# 2_P1_schdoc.net
KiCad netlist of a schematic drawn in Altium Designer
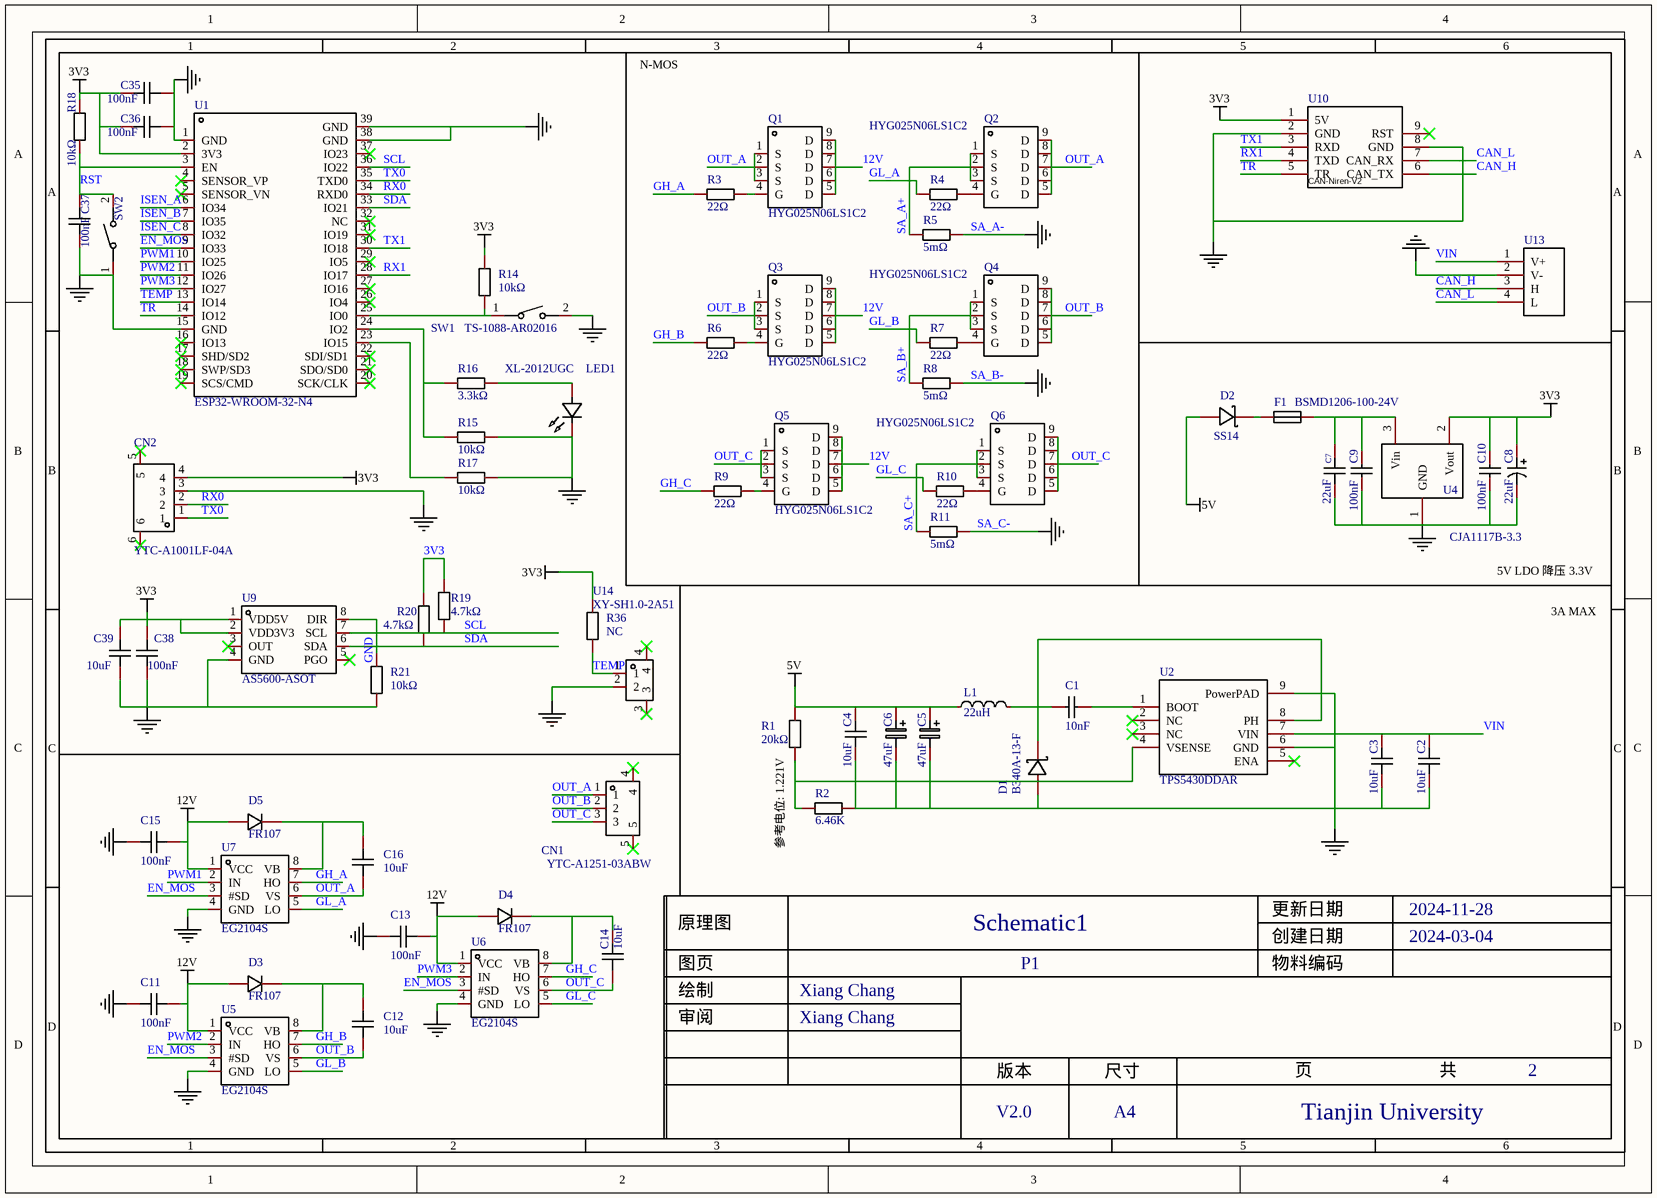
[diagram p0: 2_P1.schdoc.schdoc]

(export (version "E")
  (design (tool "Eeschema 10.0.6"))
  (components
    (comp (ref "C1")
      (value "10nF")
      (fields
        (field (name "NAME") "10nF")
        (field (name "MANUFACTURER") "YAGEO(国巨)")
        (field (name "MANUFACTURER PART") "CC0603KRX7R9BB103")
        (field (name "TOLERANCE") "±10%")
      )
      (libsource (lib "altium-import") (part "root_0_CC0603KRX7R9BB103_"))
    )
    (comp (ref "C2")
      (value "10uF")
      (fields
        (field (name "NAME") "10uF")
        (field (name "MANUFACTURER") "muRata(村田)")
        (field (name "MANUFACTURER PART") "GRM21BR61H106KE43L")
        (field (name "TOLERANCE") "±10%")
      )
      (libsource (lib "altium-import") (part "root_1_GRM21BR61H106KE43L_"))
    )
    (comp (ref "C3")
      (value "10uF")
      (fields
        (field (name "NAME") "10uF")
        (field (name "MANUFACTURER") "muRata(村田)")
        (field (name "MANUFACTURER PART") "GRM21BR61H106KE43L")
        (field (name "TOLERANCE") "±10%")
      )
      (libsource (lib "altium-import") (part "root_1_GRM21BR61H106KE43L_"))
    )
    (comp (ref "C4")
      (value "10uF")
      (fields
        (field (name "NAME") "10uF")
        (field (name "MANUFACTURER") "muRata(村田)")
        (field (name "MANUFACTURER PART") "GRM21BR61H106KE43L")
        (field (name "TOLERANCE") "±10%")
      )
      (libsource (lib "altium-import") (part "root_1_GRM21BR61H106KE43L_"))
    )
    (comp (ref "C5")
      (value "47uF")
      (fields
        (field (name "NAME") "47uF")
        (field (name "MANUFACTURER") "CEC(振华新云)")
        (field (name "MANUFACTURER PART") "CA45-B-16V-47uF-K")
        (field (name "TOLERANCE") "±10%")
      )
      (libsource (lib "altium-import") (part "root_1_CA45-B-16V-47uF-K_"))
    )
    (comp (ref "C6")
      (value "47uF")
      (fields
        (field (name "NAME") "47uF")
        (field (name "MANUFACTURER") "CEC(振华新云)")
        (field (name "MANUFACTURER PART") "CA45-B-16V-47uF-K")
        (field (name "TOLERANCE") "±10%")
      )
      (libsource (lib "altium-import") (part "root_1_CA45-B-16V-47uF-K_"))
    )
    (comp (ref "C7")
      (value "22uF")
      (fields
        (field (name "NAME") "22uF")
        (field (name "MANUFACTURER") "SAMSUNG(三星)")
        (field (name "MANUFACTURER PART") "CL10A226MO7JZNC")
        (field (name "TOLERANCE") "±20%")
      )
      (libsource (lib "altium-import") (part "root_1_CL10A226MO7JZNC_"))
    )
    (comp (ref "C8")
      (value "22uF")
      (fields
        (field (name "NAME") "22uF")
        (field (name "MANUFACTURER") "CEC(振华新云)")
        (field (name "MANUFACTURER PART") "CA45-A-16V-22uF-K")
        (field (name "TOLERANCE") "±10%")
      )
      (libsource (lib "altium-import") (part "root_3_CA45-A-16V-22uF-K_"))
    )
    (comp (ref "C9")
      (value "100nF")
      (fields
        (field (name "NAME") "100nF")
        (field (name "MANUFACTURER") "SAMSUNG(三星)")
        (field (name "MANUFACTURER PART") "CL05B104KB54PNC")
        (field (name "TOLERANCE") "±10%")
      )
      (libsource (lib "altium-import") (part "root_1_CL05B104KB54PNC_"))
    )
    (comp (ref "C10")
      (value "100nF")
      (fields
        (field (name "NAME") "100nF")
        (field (name "MANUFACTURER") "SAMSUNG(三星)")
        (field (name "MANUFACTURER PART") "CL05B104KB54PNC")
        (field (name "TOLERANCE") "±10%")
      )
      (libsource (lib "altium-import") (part "root_1_CL05B104KB54PNC_"))
    )
    (comp (ref "C11")
      (value "100nF")
      (fields
        (field (name "NAME") "100nF")
        (field (name "MANUFACTURER") "FH(风华)")
        (field (name "MANUFACTURER PART") "0603B104K500NT")
        (field (name "TOLERANCE") "±10%")
      )
      (libsource (lib "altium-import") (part "root_0_0603B104K500NT_"))
    )
    (comp (ref "C12")
      (value "10uF")
      (fields
        (field (name "NAME") "10uF")
        (field (name "MANUFACTURER") "muRata(村田)")
        (field (name "MANUFACTURER PART") "GRM21BR61H106KE43L")
        (field (name "TOLERANCE") "±10%")
      )
      (libsource (lib "altium-import") (part "root_1_GRM21BR61H106KE43L_"))
    )
    (comp (ref "C13")
      (value "100nF")
      (fields
        (field (name "NAME") "100nF")
        (field (name "MANUFACTURER") "FH(风华)")
        (field (name "MANUFACTURER PART") "0603B104K500NT")
        (field (name "TOLERANCE") "±10%")
      )
      (libsource (lib "altium-import") (part "root_0_0603B104K500NT_"))
    )
    (comp (ref "C14")
      (value "10uF")
      (fields
        (field (name "NAME") "10uF")
        (field (name "MANUFACTURER") "muRata(村田)")
        (field (name "MANUFACTURER PART") "GRM21BR61H106KE43L")
        (field (name "TOLERANCE") "±10%")
      )
      (libsource (lib "altium-import") (part "root_1_GRM21BR61H106KE43L_"))
    )
    (comp (ref "C15")
      (value "100nF")
      (fields
        (field (name "NAME") "100nF")
        (field (name "MANUFACTURER") "FH(风华)")
        (field (name "MANUFACTURER PART") "0603B104K500NT")
        (field (name "TOLERANCE") "±10%")
      )
      (libsource (lib "altium-import") (part "root_0_0603B104K500NT_"))
    )
    (comp (ref "C16")
      (value "10uF")
      (fields
        (field (name "NAME") "10uF")
        (field (name "MANUFACTURER") "muRata(村田)")
        (field (name "MANUFACTURER PART") "GRM21BR61H106KE43L")
        (field (name "TOLERANCE") "±10%")
      )
      (libsource (lib "altium-import") (part "root_1_GRM21BR61H106KE43L_"))
    )
    (comp (ref "C35")
      (value "100nF")
      (fields
        (field (name "NAME") "100nF")
        (field (name "MANUFACTURER") "FH(风华)")
        (field (name "MANUFACTURER PART") "0603B104K500NT")
        (field (name "TOLERANCE") "±10%")
      )
      (libsource (lib "altium-import") (part "root_0_0603B104K500NT_"))
    )
    (comp (ref "C36")
      (value "100nF")
      (fields
        (field (name "NAME") "100nF")
        (field (name "MANUFACTURER") "FH(风华)")
        (field (name "MANUFACTURER PART") "0603B104K500NT")
        (field (name "TOLERANCE") "±10%")
      )
      (libsource (lib "altium-import") (part "root_0_0603B104K500NT_"))
    )
    (comp (ref "C37")
      (value "100nF")
      (fields
        (field (name "NAME") "100nF")
        (field (name "MANUFACTURER") "FH(风华)")
        (field (name "MANUFACTURER PART") "0603B104K500NT")
        (field (name "TOLERANCE") "±10%")
      )
      (libsource (lib "altium-import") (part "root_1_0603B104K500NT_"))
    )
    (comp (ref "C38")
      (value "100nF")
      (fields
        (field (name "NAME") "100nF")
        (field (name "MANUFACTURER") "YAGEO(国巨)")
        (field (name "MANUFACTURER PART") "CC0603KRX7R9BB104")
        (field (name "TOLERANCE") "±10%")
      )
      (libsource (lib "altium-import") (part "root_1_CC0603KRX7R9BB104_"))
    )
    (comp (ref "C39")
      (value "10uF")
      (fields
        (field (name "NAME") "10uF")
        (field (name "MANUFACTURER") "muRata(村田)")
        (field (name "MANUFACTURER PART") "GRM21BR61H106KE43L")
        (field (name "TOLERANCE") "±10%")
      )
      (libsource (lib "altium-import") (part "root_1_GRM21BR61H106KE43L_"))
    )
    (comp (ref "CN1")
      (value "YTC-A1251-03ABW")
      (description "插针结构:1x3P;间距:1.25mm;安装方式:卧贴;总PIN数:3P;排数:1;每排PIN数:3;额定电流:1A;工作温度范围:-25℃~+85℃;")
      (fields (field (name "NAME") "YTC-A1251-03ABW") (field (name "MANUFACTURER") "YIYUAN(怡远)"))
      (libsource (lib "altium-import") (part "root_0_YTC-A1251-03ABW_"))
    )
    (comp (ref "CN2")
      (value "YTC-A1001LF-04A")
      (description "插针结构:1x4P;间距:1mm;安装方式:立贴;总PIN数:4P;排数:1;每排PIN数:4;额定电流:1A;工作温度范围:-25℃~+85℃;")
      (fields (field (name "NAME") "YTC-A1001LF-04A") (field (name "MANUFACTURER") "YIYUAN(怡远)"))
      (libsource (lib "altium-import") (part "root_2_YTC-A1001LF-04A_"))
    )
    (comp (ref "D1")
      (value "B340A-13-F")
      (description "正向压降(Vf):500mV@3A;直流反向耐压(Vr):40V;平均整流电流(Io):3A;")
      (fields (field (name "NAME") "B340A-13-F") (field (name "MANUFACTURER") "DIODES(美台)"))
      (libsource (lib "altium-import") (part "root_3_B340A-13-F_"))
    )
    (comp (ref "D2")
      (value "SS14")
      (description "二极管配置:独立式;正向压降(Vf):550mV@1A;直流反向耐压(Vr):40V;平均整流电流(Io):1A;")
      (fields (field (name "NAME") "SS14") (field (name "MANUFACTURER") "MDD"))
      (libsource (lib "altium-import") (part "root_2_SS14_C2480_"))
    )
    (comp (ref "D3")
      (value "FR107")
      (description "二极管配置:-;正向压降(Vf):1.3V@1A;直流反向耐压(Vr):1kV;平均整流电流(Io):1A;反向恢复时间(trr):500ns;")
      (fields (field (name "NAME") "FR107") (field (name "MANUFACTURER") "BORN(伯恩半导体)"))
      (libsource (lib "altium-import") (part "root_2_FR107_C511885_"))
    )
    (comp (ref "D4")
      (value "FR107")
      (description "二极管配置:-;正向压降(Vf):1.3V@1A;直流反向耐压(Vr):1kV;平均整流电流(Io):1A;反向恢复时间(trr):500ns;")
      (fields (field (name "NAME") "FR107") (field (name "MANUFACTURER") "BORN(伯恩半导体)"))
      (libsource (lib "altium-import") (part "root_2_FR107_C511885_"))
    )
    (comp (ref "D5")
      (value "FR107")
      (description "二极管配置:-;正向压降(Vf):1.3V@1A;直流反向耐压(Vr):1kV;平均整流电流(Io):1A;反向恢复时间(trr):500ns;")
      (fields (field (name "NAME") "FR107") (field (name "MANUFACTURER") "BORN(伯恩半导体)"))
      (libsource (lib "altium-import") (part "root_2_FR107_C511885_"))
    )
    (comp (ref "F1")
      (value "BSMD1206-100-24V")
      (description "最大电压:24V;最大电流:40A;保持电流:1A;跳闸电流:1.8A;")
      (fields (field (name "NAME") "BSMD1206-100-24V") (field (name "MANUFACTURER") "BHFUSE(佰宏)"))
      (libsource (lib "altium-import") (part "root_0_BSMD1206-100-24V_"))
    )
    (comp (ref "L1")
      (value "22uH")
      (fields
        (field (name "NAME") "22uH")
        (field (name "MANUFACTURER") "cjiang(长江微电)")
        (field (name "MANUFACTURER PART") "FXL0630-220-M")
        (field (name "TOLERANCE") "±20%")
      )
      (libsource (lib "altium-import") (part "root_0_FXL0630-220-M_"))
    )
    (comp (ref "LED1")
      (value "XL-2012UGC")
      (description "发光颜色:翠绿色;功率:80mW;正向电流:25mA;主波长:516nm~525nm;透镜颜色:无色透明透镜;色温:-;发光角度:120°;载带方式:正贴;工作温度:-30℃~+85℃;")
      (fields (field (name "NAME") "XL-2012UGC") (field (name "MANUFACTURER") "XINGLIGHT(成兴光)"))
      (libsource (lib "altium-import") (part "root_1_XL-2012UGC_"))
    )
    (comp (ref "Q1")
      (value "HYG025N06LS1C2")
      (fields (field (name "NAME") "HYG025N06LS1C2") (field (name "MANUFACTURER") "HUAYI(华羿微)"))
      (libsource (lib "altium-import") (part "root_0_HYG025N06LS1C2_"))
    )
    (comp (ref "Q2")
      (value "HYG025N06LS1C2")
      (fields (field (name "NAME") "HYG025N06LS1C2") (field (name "MANUFACTURER") "HUAYI(华羿微)"))
      (libsource (lib "altium-import") (part "root_0_HYG025N06LS1C2_"))
    )
    (comp (ref "Q3")
      (value "HYG025N06LS1C2")
      (fields (field (name "NAME") "HYG025N06LS1C2") (field (name "MANUFACTURER") "HUAYI(华羿微)"))
      (libsource (lib "altium-import") (part "root_0_HYG025N06LS1C2_"))
    )
    (comp (ref "Q4")
      (value "HYG025N06LS1C2")
      (fields (field (name "NAME") "HYG025N06LS1C2") (field (name "MANUFACTURER") "HUAYI(华羿微)"))
      (libsource (lib "altium-import") (part "root_0_HYG025N06LS1C2_"))
    )
    (comp (ref "Q5")
      (value "HYG025N06LS1C2")
      (fields (field (name "NAME") "HYG025N06LS1C2") (field (name "MANUFACTURER") "HUAYI(华羿微)"))
      (libsource (lib "altium-import") (part "root_0_HYG025N06LS1C2_"))
    )
    (comp (ref "Q6")
      (value "HYG025N06LS1C2")
      (fields (field (name "NAME") "HYG025N06LS1C2") (field (name "MANUFACTURER") "HUAYI(华羿微)"))
      (libsource (lib "altium-import") (part "root_0_HYG025N06LS1C2_"))
    )
    (comp (ref "R1")
      (value "20kΩ")
      (fields
        (field (name "NAME") "20kΩ")
        (field (name "MANUFACTURER") "UNI-ROYAL(厚声)")
        (field (name "MANUFACTURER PART") "0603WAF2002T5E")
        (field (name "TOLERANCE") "±1%")
      )
      (libsource (lib "altium-import") (part "root_1_0603WAF2002T5E_"))
    )
    (comp (ref "R2")
      (value "6.46K")
      (fields (field (name "NAME") "6.46K"))
      (libsource (lib "altium-import") (part "root_2_Res_0603_"))
    )
    (comp (ref "R3")
      (value "22Ω")
      (fields
        (field (name "NAME") "22Ω")
        (field (name "MANUFACTURER") "UNI-ROYAL(厚声)")
        (field (name "MANUFACTURER PART") "0603WAF220JT5E")
        (field (name "TOLERANCE") "±1%")
      )
      (libsource (lib "altium-import") (part "root_0_0603WAF220JT5E_"))
    )
    (comp (ref "R4")
      (value "22Ω")
      (fields
        (field (name "NAME") "22Ω")
        (field (name "MANUFACTURER") "UNI-ROYAL(厚声)")
        (field (name "MANUFACTURER PART") "0603WAF220JT5E")
        (field (name "TOLERANCE") "±1%")
      )
      (libsource (lib "altium-import") (part "root_0_0603WAF220JT5E_"))
    )
    (comp (ref "R5")
      (value "5mΩ")
      (fields
        (field (name "NAME") "5mΩ")
        (field (name "MANUFACTURER") "大毅科技")
        (field (name "MANUFACTURER PART") "RLP25FEGMR005")
        (field (name "TOLERANCE") "±1%")
      )
      (libsource (lib "altium-import") (part "root_2_RLP25FEGMR005_"))
    )
    (comp (ref "R6")
      (value "22Ω")
      (fields
        (field (name "NAME") "22Ω")
        (field (name "MANUFACTURER") "UNI-ROYAL(厚声)")
        (field (name "MANUFACTURER PART") "0603WAF220JT5E")
        (field (name "TOLERANCE") "±1%")
      )
      (libsource (lib "altium-import") (part "root_0_0603WAF220JT5E_"))
    )
    (comp (ref "R7")
      (value "22Ω")
      (fields
        (field (name "NAME") "22Ω")
        (field (name "MANUFACTURER") "UNI-ROYAL(厚声)")
        (field (name "MANUFACTURER PART") "0603WAF220JT5E")
        (field (name "TOLERANCE") "±1%")
      )
      (libsource (lib "altium-import") (part "root_0_0603WAF220JT5E_"))
    )
    (comp (ref "R8")
      (value "5mΩ")
      (fields
        (field (name "NAME") "5mΩ")
        (field (name "MANUFACTURER") "大毅科技")
        (field (name "MANUFACTURER PART") "RLP25FEGMR005")
        (field (name "TOLERANCE") "±1%")
      )
      (libsource (lib "altium-import") (part "root_2_RLP25FEGMR005_"))
    )
    (comp (ref "R9")
      (value "22Ω")
      (fields
        (field (name "NAME") "22Ω")
        (field (name "MANUFACTURER") "UNI-ROYAL(厚声)")
        (field (name "MANUFACTURER PART") "0603WAF220JT5E")
        (field (name "TOLERANCE") "±1%")
      )
      (libsource (lib "altium-import") (part "root_0_0603WAF220JT5E_"))
    )
    (comp (ref "R10")
      (value "22Ω")
      (fields
        (field (name "NAME") "22Ω")
        (field (name "MANUFACTURER") "UNI-ROYAL(厚声)")
        (field (name "MANUFACTURER PART") "0603WAF220JT5E")
        (field (name "TOLERANCE") "±1%")
      )
      (libsource (lib "altium-import") (part "root_0_0603WAF220JT5E_"))
    )
    (comp (ref "R11")
      (value "5mΩ")
      (fields
        (field (name "NAME") "5mΩ")
        (field (name "MANUFACTURER") "大毅科技")
        (field (name "MANUFACTURER PART") "RLP25FEGMR005")
        (field (name "TOLERANCE") "±1%")
      )
      (libsource (lib "altium-import") (part "root_2_RLP25FEGMR005_"))
    )
    (comp (ref "R14")
      (value "10kΩ")
      (fields
        (field (name "NAME") "10kΩ")
        (field (name "MANUFACTURER") "UNI-ROYAL(厚声)")
        (field (name "MANUFACTURER PART") "0603WAF1002T5E")
        (field (name "TOLERANCE") "±1%")
      )
      (libsource (lib "altium-import") (part "root_1_0603WAF1002T5E_"))
    )
    (comp (ref "R15")
      (value "10kΩ")
      (fields
        (field (name "NAME") "10kΩ")
        (field (name "MANUFACTURER") "UNI-ROYAL(厚声)")
        (field (name "MANUFACTURER PART") "0603WAF1002T5E")
        (field (name "TOLERANCE") "±1%")
      )
      (libsource (lib "altium-import") (part "root_0_0603WAF1002T5E_"))
    )
    (comp (ref "R16")
      (value "3.3kΩ")
      (fields
        (field (name "NAME") "3.3kΩ")
        (field (name "MANUFACTURER") "UNI-ROYAL(厚声)")
        (field (name "MANUFACTURER PART") "0603WAF3301T5E")
        (field (name "TOLERANCE") "±1%")
      )
      (libsource (lib "altium-import") (part "root_0_0603WAF3301T5E_"))
    )
    (comp (ref "R17")
      (value "10kΩ")
      (fields
        (field (name "NAME") "10kΩ")
        (field (name "MANUFACTURER") "UNI-ROYAL(厚声)")
        (field (name "MANUFACTURER PART") "0603WAF1002T5E")
        (field (name "TOLERANCE") "±1%")
      )
      (libsource (lib "altium-import") (part "root_0_0603WAF1002T5E_"))
    )
    (comp (ref "R18")
      (value "10kΩ")
      (fields
        (field (name "NAME") "10kΩ")
        (field (name "MANUFACTURER") "UNI-ROYAL(厚声)")
        (field (name "MANUFACTURER PART") "0603WAF1002T5E")
        (field (name "TOLERANCE") "±1%")
      )
      (libsource (lib "altium-import") (part "root_1_0603WAF1002T5E_"))
    )
    (comp (ref "R19")
      (value "4.7kΩ")
      (fields
        (field (name "NAME") "4.7kΩ")
        (field (name "MANUFACTURER") "UNI-ROYAL(厚声)")
        (field (name "MANUFACTURER PART") "0603WAF4701T5E")
        (field (name "TOLERANCE") "±1%")
      )
      (libsource (lib "altium-import") (part "root_1_0603WAF4701T5E_"))
    )
    (comp (ref "R20")
      (value "4.7kΩ")
      (fields
        (field (name "NAME") "4.7kΩ")
        (field (name "MANUFACTURER") "UNI-ROYAL(厚声)")
        (field (name "MANUFACTURER PART") "0603WAF4701T5E")
        (field (name "TOLERANCE") "±1%")
      )
      (libsource (lib "altium-import") (part "root_1_0603WAF4701T5E_"))
    )
    (comp (ref "R21")
      (value "10kΩ")
      (fields
        (field (name "NAME") "10kΩ")
        (field (name "MANUFACTURER") "UNI-ROYAL(厚声)")
        (field (name "MANUFACTURER PART") "0603WAF1002T5E")
        (field (name "TOLERANCE") "±1%")
      )
      (libsource (lib "altium-import") (part "root_1_0603WAF1002T5E_"))
    )
    (comp (ref "R36")
      (value "NC")
      (fields (field (name "NAME") "NC"))
      (libsource (lib "altium-import") (part "root_1_Res_0603_"))
    )
    (comp (ref "SW1")
      (value "TS-1088-AR02016")
      (fields (field (name "NAME") "TS-1088-AR02016") (field (name "MANUFACTURER") "XUNPU(讯普)"))
      (libsource (lib "altium-import") (part "root_0_TS-1088-AR02016_"))
    )
    (comp (ref "SW2")
      (value "TS-1088-AR02016")
      (fields (field (name "MANUFACTURER") "XUNPU(讯普)"))
      (libsource (lib "altium-import") (part "root_1_TS-1088-AR02016_"))
    )
    (comp (ref "U1")
      (value "ESP32-WROOM-32-N4")
      (description "WiFi+蓝牙4.2+双核CPU,ESP32")
      (fields (field (name "NAME") "ESP32-WROOM-32-N4") (field (name "MANUFACTURER") "ESPRESSIF(乐鑫)"))
      (libsource (lib "altium-import") (part "root_0_ESP32-WROOM-32-N4_"))
    )
    (comp (ref "U2")
      (value "TPS5430DDAR")
      (description "功能类型:降压型;输出类型:可调;输入电压:5.5V~36V;输出电压:1.221V~32.04V;输出电流(最大值):3A;")
      (fields (field (name "NAME") "TPS5430DDAR") (field (name "MANUFACTURER") "TI(德州仪器)"))
      (libsource (lib "altium-import") (part "root_0_TPS5430DDAR_"))
    )
    (comp (ref "U4")
      (value "CJA1117B-3.3")
      (description "输出类型:固定;最大输入电压:15V;输出电压:3.3V;输出电流:1A;电源纹波抑制比(PSRR):75dB@(120Hz);输出极性:正;")
      (fields (field (name "NAME") "CJA1117B-3.3") (field (name "MANUFACTURER") "CJ(江苏长电/长晶)"))
      (libsource (lib "altium-import") (part "root_1_CJA1117B-3.3_"))
    )
    (comp (ref "U5")
      (value "EG2104S")
      (fields (field (name "NAME") "EG2104S") (field (name "MANUFACTURER") "EG(屹晶微)"))
      (libsource (lib "altium-import") (part "root_0_EG2104S_"))
    )
    (comp (ref "U6")
      (value "EG2104S")
      (fields (field (name "NAME") "EG2104S") (field (name "MANUFACTURER") "EG(屹晶微)"))
      (libsource (lib "altium-import") (part "root_0_EG2104S_"))
    )
    (comp (ref "U7")
      (value "EG2104S")
      (fields (field (name "NAME") "EG2104S") (field (name "MANUFACTURER") "EG(屹晶微)"))
      (libsource (lib "altium-import") (part "root_0_EG2104S_"))
    )
    (comp (ref "U9")
      (value "AS5600-ASOT")
      (fields (field (name "NAME") "AS5600-ASOT") (field (name "MANUFACTURER") "ams(艾迈斯半导体)"))
      (libsource (lib "altium-import") (part "root_0_AS5600-ASOT_"))
    )
    (comp (ref "U10")
      (value "CAN-Niren-V2")
      (description "CAN-Niren-V2")
      (libsource (lib "altium-import") (part "root_0_CAN-Niren-V2_"))
    )
    (comp (ref "U13")
      (value "XT30PB(2+2)-M")
      (libsource (lib "altium-import") (part "root_0_XT30PB(2+2)-M_"))
    )
    (comp (ref "U14")
      (value "XY-SH1.0-2A51")
      (description "插针结构:1x2P;间距:1mm;安装方式:立贴;总PIN数:2P;排数:1;每排PIN数:2;")
      (fields (field (name "NAME") "XY-SH1.0-2A51") (field (name "MANUFACTURER") "XYECONN(辛译)"))
      (libsource (lib "altium-import") (part "root_0_XY-SH1.0-2A51_"))
    )
  )
  (nets
    (net (code "1") (name "/CAN_H") (class "Default")
      (node (ref "U10") (pin "6") (pinfunction "CAN_TX_6") (pintype "passive"))
      (node (ref "U13") (pin "3") (pinfunction "H_3") (pintype "passive"))
    )
    (net (code "2") (name "/CAN_L") (class "Default")
      (node (ref "U10") (pin "7") (pinfunction "CAN_RX_7") (pintype "passive"))
      (node (ref "U13") (pin "4") (pinfunction "L_4") (pintype "passive"))
    )
    (net (code "3") (name "/EN_MOS") (class "Default")
      (node (ref "U1") (pin "9") (pinfunction "IO33_9") (pintype "passive"))
      (node (ref "U5") (pin "3") (pinfunction "#SD_3") (pintype "passive"))
      (node (ref "U6") (pin "3") (pinfunction "#SD_3") (pintype "passive"))
      (node (ref "U7") (pin "3") (pinfunction "#SD_3") (pintype "passive"))
    )
    (net (code "4") (name "/GH_A") (class "Default")
      (node (ref "R3") (pin "1") (pinfunction "1_1") (pintype "passive"))
      (node (ref "U7") (pin "7") (pinfunction "HO_7") (pintype "passive"))
    )
    (net (code "5") (name "/GH_B") (class "Default")
      (node (ref "R6") (pin "1") (pinfunction "1_1") (pintype "passive"))
      (node (ref "U5") (pin "7") (pinfunction "HO_7") (pintype "passive"))
    )
    (net (code "6") (name "/GH_C") (class "Default")
      (node (ref "R9") (pin "1") (pinfunction "1_1") (pintype "passive"))
      (node (ref "U6") (pin "7") (pinfunction "HO_7") (pintype "passive"))
    )
    (net (code "7") (name "/GL_A") (class "Default")
      (node (ref "R4") (pin "1") (pinfunction "1_1") (pintype "passive"))
      (node (ref "U7") (pin "5") (pinfunction "LO_5") (pintype "passive"))
    )
    (net (code "8") (name "/GL_B") (class "Default")
      (node (ref "R7") (pin "1") (pinfunction "1_1") (pintype "passive"))
      (node (ref "U5") (pin "5") (pinfunction "LO_5") (pintype "passive"))
    )
    (net (code "9") (name "/GL_C") (class "Default")
      (node (ref "R10") (pin "1") (pinfunction "1_1") (pintype "passive"))
      (node (ref "U6") (pin "5") (pinfunction "LO_5") (pintype "passive"))
    )
    (net (code "10") (name "/ISEN_A") (class "Default")
      (node (ref "U1") (pin "6") (pinfunction "IO34_6") (pintype "passive"))
    )
    (net (code "11") (name "/ISEN_B") (class "Default")
      (node (ref "U1") (pin "7") (pinfunction "IO35_7") (pintype "passive"))
    )
    (net (code "12") (name "/ISEN_C") (class "Default")
      (node (ref "U1") (pin "8") (pinfunction "IO32_8") (pintype "passive"))
    )
    (net (code "13") (name "/OUT_A") (class "Default")
      (node (ref "C16") (pin "1") (pinfunction "1_1") (pintype "passive"))
      (node (ref "CN1") (pin "1") (pinfunction "1_1") (pintype "passive"))
      (node (ref "Q1") (pin "1") (pinfunction "S_1") (pintype "passive"))
      (node (ref "Q1") (pin "2") (pinfunction "S_2") (pintype "passive"))
      (node (ref "Q1") (pin "3") (pinfunction "S_3") (pintype "passive"))
      (node (ref "Q2") (pin "5") (pinfunction "D_5") (pintype "passive"))
      (node (ref "Q2") (pin "6") (pinfunction "D_6") (pintype "passive"))
      (node (ref "Q2") (pin "7") (pinfunction "D_7") (pintype "passive"))
      (node (ref "Q2") (pin "8") (pinfunction "D_8") (pintype "passive"))
      (node (ref "Q2") (pin "9") (pinfunction "D_9") (pintype "passive"))
      (node (ref "U7") (pin "6") (pinfunction "VS_6") (pintype "passive"))
    )
    (net (code "14") (name "/OUT_B") (class "Default")
      (node (ref "C12") (pin "1") (pinfunction "1_1") (pintype "passive"))
      (node (ref "CN1") (pin "2") (pinfunction "2_2") (pintype "passive"))
      (node (ref "Q3") (pin "1") (pinfunction "S_1") (pintype "passive"))
      (node (ref "Q3") (pin "2") (pinfunction "S_2") (pintype "passive"))
      (node (ref "Q3") (pin "3") (pinfunction "S_3") (pintype "passive"))
      (node (ref "Q4") (pin "5") (pinfunction "D_5") (pintype "passive"))
      (node (ref "Q4") (pin "6") (pinfunction "D_6") (pintype "passive"))
      (node (ref "Q4") (pin "7") (pinfunction "D_7") (pintype "passive"))
      (node (ref "Q4") (pin "8") (pinfunction "D_8") (pintype "passive"))
      (node (ref "Q4") (pin "9") (pinfunction "D_9") (pintype "passive"))
      (node (ref "U5") (pin "6") (pinfunction "VS_6") (pintype "passive"))
    )
    (net (code "15") (name "/OUT_C") (class "Default")
      (node (ref "C14") (pin "1") (pinfunction "1_1") (pintype "passive"))
      (node (ref "CN1") (pin "3") (pinfunction "3_3") (pintype "passive"))
      (node (ref "Q5") (pin "1") (pinfunction "S_1") (pintype "passive"))
      (node (ref "Q5") (pin "2") (pinfunction "S_2") (pintype "passive"))
      (node (ref "Q5") (pin "3") (pinfunction "S_3") (pintype "passive"))
      (node (ref "Q6") (pin "5") (pinfunction "D_5") (pintype "passive"))
      (node (ref "Q6") (pin "6") (pinfunction "D_6") (pintype "passive"))
      (node (ref "Q6") (pin "7") (pinfunction "D_7") (pintype "passive"))
      (node (ref "Q6") (pin "8") (pinfunction "D_8") (pintype "passive"))
      (node (ref "Q6") (pin "9") (pinfunction "D_9") (pintype "passive"))
      (node (ref "U6") (pin "6") (pinfunction "VS_6") (pintype "passive"))
    )
    (net (code "16") (name "/PWM1") (class "Default")
      (node (ref "U1") (pin "10") (pinfunction "IO25_10") (pintype "passive"))
      (node (ref "U7") (pin "2") (pinfunction "IN_2") (pintype "passive"))
    )
    (net (code "17") (name "/PWM2") (class "Default")
      (node (ref "U1") (pin "11") (pinfunction "IO26_11") (pintype "passive"))
      (node (ref "U5") (pin "2") (pinfunction "IN_2") (pintype "passive"))
    )
    (net (code "18") (name "/PWM3") (class "Default")
      (node (ref "U1") (pin "12") (pinfunction "IO27_12") (pintype "passive"))
      (node (ref "U6") (pin "2") (pinfunction "IN_2") (pintype "passive"))
    )
    (net (code "19") (name "/RST") (class "Default")
      (node (ref "C37") (pin "2") (pinfunction "2_2") (pintype "passive"))
      (node (ref "R18") (pin "1") (pinfunction "1_1") (pintype "passive"))
      (node (ref "SW2") (pin "2") (pinfunction "2_2") (pintype "passive"))
      (node (ref "U1") (pin "3") (pinfunction "EN_3") (pintype "passive"))
    )
    (net (code "20") (name "/RX0") (class "Default")
      (node (ref "CN2") (pin "2") (pinfunction "2_2") (pintype "passive"))
      (node (ref "U1") (pin "34") (pinfunction "RXD0_34") (pintype "passive"))
    )
    (net (code "21") (name "/RX1") (class "Default")
      (node (ref "U1") (pin "28") (pinfunction "IO17_28") (pintype "passive"))
      (node (ref "U10") (pin "4") (pinfunction "TXD_4") (pintype "passive"))
    )
    (net (code "22") (name "/SA_A+") (class "Default")
      (node (ref "Q2") (pin "1") (pinfunction "S_1") (pintype "passive"))
      (node (ref "Q2") (pin "2") (pinfunction "S_2") (pintype "passive"))
      (node (ref "Q2") (pin "3") (pinfunction "S_3") (pintype "passive"))
      (node (ref "R5") (pin "2") (pinfunction "2_2") (pintype "passive"))
    )
    (net (code "23") (name "/SA_B+") (class "Default")
      (node (ref "Q4") (pin "1") (pinfunction "S_1") (pintype "passive"))
      (node (ref "Q4") (pin "2") (pinfunction "S_2") (pintype "passive"))
      (node (ref "Q4") (pin "3") (pinfunction "S_3") (pintype "passive"))
      (node (ref "R8") (pin "2") (pinfunction "2_2") (pintype "passive"))
    )
    (net (code "24") (name "/SA_C+") (class "Default")
      (node (ref "Q6") (pin "1") (pinfunction "S_1") (pintype "passive"))
      (node (ref "Q6") (pin "2") (pinfunction "S_2") (pintype "passive"))
      (node (ref "Q6") (pin "3") (pinfunction "S_3") (pintype "passive"))
      (node (ref "R11") (pin "2") (pinfunction "2_2") (pintype "passive"))
    )
    (net (code "25") (name "/SCL") (class "Default")
      (node (ref "R19") (pin "1") (pinfunction "1_1") (pintype "passive"))
      (node (ref "U1") (pin "36") (pinfunction "IO22_36") (pintype "passive"))
      (node (ref "U9") (pin "7") (pinfunction "SCL_7") (pintype "passive"))
    )
    (net (code "26") (name "/SDA") (class "Default")
      (node (ref "R20") (pin "1") (pinfunction "1_1") (pintype "passive"))
      (node (ref "U1") (pin "33") (pinfunction "IO21_33") (pintype "passive"))
      (node (ref "U9") (pin "6") (pinfunction "SDA_6") (pintype "passive"))
    )
    (net (code "27") (name "/TEMP") (class "Default")
      (node (ref "R36") (pin "1") (pinfunction "1_1") (pintype "passive"))
      (node (ref "U1") (pin "13") (pinfunction "IO14_13") (pintype "passive"))
      (node (ref "U14") (pin "1") (pinfunction "1_1") (pintype "passive"))
    )
    (net (code "28") (name "/TR") (class "Default")
      (node (ref "U1") (pin "14") (pinfunction "IO12_14") (pintype "passive"))
      (node (ref "U10") (pin "5") (pinfunction "TR_5") (pintype "passive"))
    )
    (net (code "29") (name "/TX0") (class "Default")
      (node (ref "CN2") (pin "1") (pinfunction "1_1") (pintype "passive"))
      (node (ref "U1") (pin "35") (pinfunction "TXD0_35") (pintype "passive"))
    )
    (net (code "30") (name "/TX1") (class "Default")
      (node (ref "U1") (pin "30") (pinfunction "IO18_30") (pintype "passive"))
      (node (ref "U10") (pin "3") (pinfunction "RXD_3") (pintype "passive"))
    )
    (net (code "31") (name "/VIN") (class "Default")
      (node (ref "C2") (pin "2") (pinfunction "2_2") (pintype "passive"))
      (node (ref "C3") (pin "2") (pinfunction "2_2") (pintype "passive"))
      (node (ref "U13") (pin "1") (pinfunction "V+_1") (pintype "passive"))
      (node (ref "U2") (pin "7") (pinfunction "VIN_7") (pintype "passive"))
    )
    (net (code "32") (name "3V3") (class "Default")
      (node (ref "C10") (pin "2") (pinfunction "2_2") (pintype "passive"))
      (node (ref "C35") (pin "1") (pinfunction "1_1") (pintype "passive"))
      (node (ref "C36") (pin "1") (pinfunction "1_1") (pintype "passive"))
      (node (ref "C38") (pin "2") (pinfunction "2_2") (pintype "passive"))
      (node (ref "C39") (pin "2") (pinfunction "2_2") (pintype "passive"))
      (node (ref "C8") (pin "1") (pinfunction "1_1") (pintype "passive"))
      (node (ref "CN2") (pin "4") (pinfunction "4_4") (pintype "passive"))
      (node (ref "R14") (pin "2") (pinfunction "2_2") (pintype "passive"))
      (node (ref "R18") (pin "2") (pinfunction "2_2") (pintype "passive"))
      (node (ref "R19") (pin "2") (pinfunction "2_2") (pintype "passive"))
      (node (ref "R20") (pin "2") (pinfunction "2_2") (pintype "passive"))
      (node (ref "R36") (pin "2") (pinfunction "2_2") (pintype "passive"))
      (node (ref "U1") (pin "2") (pinfunction "3V3_2") (pintype "passive"))
      (node (ref "U10") (pin "1") (pinfunction "5V_1") (pintype "passive"))
      (node (ref "U4") (pin "2") (pinfunction "Vout_2") (pintype "passive"))
      (node (ref "U9") (pin "1") (pinfunction "VDD5V_1") (pintype "passive"))
      (node (ref "U9") (pin "2") (pinfunction "VDD3V3_2") (pintype "passive"))
    )
    (net (code "33") (name "5V") (class "Default")
      (node (ref "C4") (pin "2") (pinfunction "2_2") (pintype "passive"))
      (node (ref "C5") (pin "1") (pinfunction "1_1") (pintype "passive"))
      (node (ref "C6") (pin "1") (pinfunction "1_1") (pintype "passive"))
      (node (ref "D2") (pin "2") (pinfunction "A_2") (pintype "passive"))
      (node (ref "L1") (pin "1") (pinfunction "1_1") (pintype "passive"))
      (node (ref "R1") (pin "2") (pinfunction "2_2") (pintype "passive"))
    )
    (net (code "34") (name "12V") (class "Default")
      (node (ref "C11") (pin "2") (pinfunction "2_2") (pintype "passive"))
      (node (ref "C13") (pin "2") (pinfunction "2_2") (pintype "passive"))
      (node (ref "C15") (pin "2") (pinfunction "2_2") (pintype "passive"))
      (node (ref "D3") (pin "2") (pinfunction "A_2") (pintype "passive"))
      (node (ref "D4") (pin "2") (pinfunction "A_2") (pintype "passive"))
      (node (ref "D5") (pin "2") (pinfunction "A_2") (pintype "passive"))
      (node (ref "Q1") (pin "5") (pinfunction "D_5") (pintype "passive"))
      (node (ref "Q1") (pin "6") (pinfunction "D_6") (pintype "passive"))
      (node (ref "Q1") (pin "7") (pinfunction "D_7") (pintype "passive"))
      (node (ref "Q1") (pin "8") (pinfunction "D_8") (pintype "passive"))
      (node (ref "Q1") (pin "9") (pinfunction "D_9") (pintype "passive"))
      (node (ref "Q3") (pin "5") (pinfunction "D_5") (pintype "passive"))
      (node (ref "Q3") (pin "6") (pinfunction "D_6") (pintype "passive"))
      (node (ref "Q3") (pin "7") (pinfunction "D_7") (pintype "passive"))
      (node (ref "Q3") (pin "8") (pinfunction "D_8") (pintype "passive"))
      (node (ref "Q3") (pin "9") (pinfunction "D_9") (pintype "passive"))
      (node (ref "Q5") (pin "5") (pinfunction "D_5") (pintype "passive"))
      (node (ref "Q5") (pin "6") (pinfunction "D_6") (pintype "passive"))
      (node (ref "Q5") (pin "7") (pinfunction "D_7") (pintype "passive"))
      (node (ref "Q5") (pin "8") (pinfunction "D_8") (pintype "passive"))
      (node (ref "Q5") (pin "9") (pinfunction "D_9") (pintype "passive"))
      (node (ref "U5") (pin "1") (pinfunction "VCC_1") (pintype "passive"))
      (node (ref "U6") (pin "1") (pinfunction "VCC_1") (pintype "passive"))
      (node (ref "U7") (pin "1") (pinfunction "VCC_1") (pintype "passive"))
    )
    (net (code "35") (name "GND") (class "Default")
      (node (ref "C10") (pin "1") (pinfunction "1_1") (pintype "passive"))
      (node (ref "C11") (pin "1") (pinfunction "1_1") (pintype "passive"))
      (node (ref "C13") (pin "1") (pinfunction "1_1") (pintype "passive"))
      (node (ref "C15") (pin "1") (pinfunction "1_1") (pintype "passive"))
      (node (ref "C2") (pin "1") (pinfunction "1_1") (pintype "passive"))
      (node (ref "C3") (pin "1") (pinfunction "1_1") (pintype "passive"))
      (node (ref "C35") (pin "2") (pinfunction "2_2") (pintype "passive"))
      (node (ref "C36") (pin "2") (pinfunction "2_2") (pintype "passive"))
      (node (ref "C37") (pin "1") (pinfunction "1_1") (pintype "passive"))
      (node (ref "C38") (pin "1") (pinfunction "1_1") (pintype "passive"))
      (node (ref "C39") (pin "1") (pinfunction "1_1") (pintype "passive"))
      (node (ref "C4") (pin "1") (pinfunction "1_1") (pintype "passive"))
      (node (ref "C5") (pin "2") (pinfunction "2_2") (pintype "passive"))
      (node (ref "C6") (pin "2") (pinfunction "2_2") (pintype "passive"))
      (node (ref "C7") (pin "2") (pinfunction "2_2") (pintype "passive"))
      (node (ref "C8") (pin "2") (pinfunction "2_2") (pintype "passive"))
      (node (ref "C9") (pin "1") (pinfunction "1_1") (pintype "passive"))
      (node (ref "CN2") (pin "3") (pinfunction "3_3") (pintype "passive"))
      (node (ref "D1") (pin "2") (pinfunction "A_2") (pintype "passive"))
      (node (ref "LED1") (pin "1") (pinfunction "K_1") (pintype "passive"))
      (node (ref "R11") (pin "1") (pinfunction "1_1") (pintype "passive"))
      (node (ref "R15") (pin "2") (pinfunction "2_2") (pintype "passive"))
      (node (ref "R17") (pin "2") (pinfunction "2_2") (pintype "passive"))
      (node (ref "R2") (pin "1") (pinfunction "1_1") (pintype "passive"))
      (node (ref "R21") (pin "1") (pinfunction "1_1") (pintype "passive"))
      (node (ref "R5") (pin "1") (pinfunction "1_1") (pintype "passive"))
      (node (ref "R8") (pin "1") (pinfunction "1_1") (pintype "passive"))
      (node (ref "SW1") (pin "2") (pinfunction "2_2") (pintype "passive"))
      (node (ref "SW2") (pin "1") (pinfunction "1_1") (pintype "passive"))
      (node (ref "U1") (pin "1") (pinfunction "GND_1") (pintype "passive"))
      (node (ref "U1") (pin "15") (pinfunction "GND_15") (pintype "passive"))
      (node (ref "U1") (pin "38") (pinfunction "GND_38") (pintype "passive"))
      (node (ref "U1") (pin "39") (pinfunction "GND_39") (pintype "passive"))
      (node (ref "U10") (pin "2") (pinfunction "GND_2") (pintype "passive"))
      (node (ref "U10") (pin "8") (pinfunction "GND_8") (pintype "passive"))
      (node (ref "U13") (pin "2") (pinfunction "V-_2") (pintype "passive"))
      (node (ref "U14") (pin "2") (pinfunction "2_2") (pintype "passive"))
      (node (ref "U2") (pin "6") (pinfunction "GND_6") (pintype "passive"))
      (node (ref "U2") (pin "9") (pinfunction "PowerPAD_9") (pintype "passive"))
      (node (ref "U4") (pin "1") (pinfunction "GND_1") (pintype "passive"))
      (node (ref "U5") (pin "4") (pinfunction "GND_4") (pintype "passive"))
      (node (ref "U6") (pin "4") (pinfunction "GND_4") (pintype "passive"))
      (node (ref "U7") (pin "4") (pinfunction "GND_4") (pintype "passive"))
      (node (ref "U9") (pin "4") (pinfunction "GND_4") (pintype "passive"))
    )
    (net (code "36") (name "Net-(D1-K)") (class "Default")
      (node (ref "C1") (pin "1") (pinfunction "1_1") (pintype "passive"))
      (node (ref "D1") (pin "1") (pinfunction "K_1") (pintype "passive"))
      (node (ref "L1") (pin "2") (pinfunction "2_2") (pintype "passive"))
      (node (ref "U2") (pin "8") (pinfunction "PH_8") (pintype "passive"))
    )
    (net (code "37") (name "Net-(D2-K)") (class "Default")
      (node (ref "D2") (pin "1") (pinfunction "K_1") (pintype "passive"))
      (node (ref "F1") (pin "1") (pinfunction "1_1") (pintype "passive"))
    )
    (net (code "38") (name "Net-(D3-K)") (class "Default")
      (node (ref "C12") (pin "2") (pinfunction "2_2") (pintype "passive"))
      (node (ref "D3") (pin "1") (pinfunction "K_1") (pintype "passive"))
      (node (ref "U5") (pin "8") (pinfunction "VB_8") (pintype "passive"))
    )
    (net (code "39") (name "Net-(D4-K)") (class "Default")
      (node (ref "C14") (pin "2") (pinfunction "2_2") (pintype "passive"))
      (node (ref "D4") (pin "1") (pinfunction "K_1") (pintype "passive"))
      (node (ref "U6") (pin "8") (pinfunction "VB_8") (pintype "passive"))
    )
    (net (code "40") (name "Net-(D5-K)") (class "Default")
      (node (ref "C16") (pin "2") (pinfunction "2_2") (pintype "passive"))
      (node (ref "D5") (pin "1") (pinfunction "K_1") (pintype "passive"))
      (node (ref "U7") (pin "8") (pinfunction "VB_8") (pintype "passive"))
    )
    (net (code "41") (name "Net-(LED1-A)") (class "Default")
      (node (ref "LED1") (pin "2") (pinfunction "A_2") (pintype "passive"))
      (node (ref "R16") (pin "2") (pinfunction "2_2") (pintype "passive"))
    )
    (net (code "42") (name "Net-(Q1-G)") (class "Default")
      (node (ref "Q1") (pin "4") (pinfunction "G_4") (pintype "passive"))
      (node (ref "R3") (pin "2") (pinfunction "2_2") (pintype "passive"))
    )
    (net (code "43") (name "Net-(Q2-G)") (class "Default")
      (node (ref "Q2") (pin "4") (pinfunction "G_4") (pintype "passive"))
      (node (ref "R4") (pin "2") (pinfunction "2_2") (pintype "passive"))
    )
    (net (code "44") (name "Net-(Q3-G)") (class "Default")
      (node (ref "Q3") (pin "4") (pinfunction "G_4") (pintype "passive"))
      (node (ref "R6") (pin "2") (pinfunction "2_2") (pintype "passive"))
    )
    (net (code "45") (name "Net-(Q4-G)") (class "Default")
      (node (ref "Q4") (pin "4") (pinfunction "G_4") (pintype "passive"))
      (node (ref "R7") (pin "2") (pinfunction "2_2") (pintype "passive"))
    )
    (net (code "46") (name "Net-(Q5-G)") (class "Default")
      (node (ref "Q5") (pin "4") (pinfunction "G_4") (pintype "passive"))
      (node (ref "R9") (pin "2") (pinfunction "2_2") (pintype "passive"))
    )
    (net (code "47") (name "Net-(Q6-G)") (class "Default")
      (node (ref "Q6") (pin "4") (pinfunction "G_4") (pintype "passive"))
      (node (ref "R10") (pin "2") (pinfunction "2_2") (pintype "passive"))
    )
    (net (code "48") (name "Net-(U1-IO0)") (class "Default")
      (node (ref "R14") (pin "1") (pinfunction "1_1") (pintype "passive"))
      (node (ref "SW1") (pin "1") (pinfunction "1_1") (pintype "passive"))
      (node (ref "U1") (pin "25") (pinfunction "IO0_25") (pintype "passive"))
    )
    (net (code "49") (name "Net-(U1-IO2)") (class "Default")
      (node (ref "R15") (pin "1") (pinfunction "1_1") (pintype "passive"))
      (node (ref "R16") (pin "1") (pinfunction "1_1") (pintype "passive"))
      (node (ref "U1") (pin "24") (pinfunction "IO2_24") (pintype "passive"))
    )
    (net (code "50") (name "Net-(U1-IO15)") (class "Default")
      (node (ref "R17") (pin "1") (pinfunction "1_1") (pintype "passive"))
      (node (ref "U1") (pin "23") (pinfunction "IO15_23") (pintype "passive"))
    )
    (net (code "51") (name "Net-(U2-BOOT)") (class "Default")
      (node (ref "C1") (pin "2") (pinfunction "2_2") (pintype "passive"))
      (node (ref "U2") (pin "1") (pinfunction "BOOT_1") (pintype "passive"))
    )
    (net (code "52") (name "Net-(U2-VSENSE)") (class "Default")
      (node (ref "R1") (pin "1") (pinfunction "1_1") (pintype "passive"))
      (node (ref "R2") (pin "2") (pinfunction "2_2") (pintype "passive"))
      (node (ref "U2") (pin "4") (pinfunction "VSENSE_4") (pintype "passive"))
    )
    (net (code "53") (name "Net-(U4-Vin)") (class "Default")
      (node (ref "C7") (pin "1") (pinfunction "1_1") (pintype "passive"))
      (node (ref "C9") (pin "2") (pinfunction "2_2") (pintype "passive"))
      (node (ref "F1") (pin "2") (pinfunction "2_2") (pintype "passive"))
      (node (ref "U4") (pin "3") (pinfunction "Vin_3") (pintype "passive"))
    )
    (net (code "54") (name "Net-(U9-DIR)") (class "Default")
      (node (ref "R21") (pin "2") (pinfunction "2_2") (pintype "passive"))
      (node (ref "U9") (pin "8") (pinfunction "DIR_8") (pintype "passive"))
    )
    (net (code "55") (name "unconnected-(CN1-Pad4)") (class "Default")
      (node (ref "CN1") (pin "4") (pinfunction "4_4") (pintype "passive+no_connect"))
    )
    (net (code "56") (name "unconnected-(CN1-Pad5)") (class "Default")
      (node (ref "CN1") (pin "5") (pinfunction "5_5") (pintype "passive+no_connect"))
    )
    (net (code "57") (name "unconnected-(CN2-Pad5)") (class "Default")
      (node (ref "CN2") (pin "5") (pinfunction "5_5") (pintype "passive+no_connect"))
    )
    (net (code "58") (name "unconnected-(CN2-Pad6)") (class "Default")
      (node (ref "CN2") (pin "6") (pinfunction "6_6") (pintype "passive+no_connect"))
    )
    (net (code "59") (name "unconnected-(U1-IO4-Pad26)") (class "Default")
      (node (ref "U1") (pin "26") (pinfunction "IO4_26") (pintype "passive+no_connect"))
    )
    (net (code "60") (name "unconnected-(U1-IO5-Pad29)") (class "Default")
      (node (ref "U1") (pin "29") (pinfunction "IO5_29") (pintype "passive+no_connect"))
    )
    (net (code "61") (name "unconnected-(U1-IO13-Pad16)") (class "Default")
      (node (ref "U1") (pin "16") (pinfunction "IO13_16") (pintype "passive+no_connect"))
    )
    (net (code "62") (name "unconnected-(U1-IO16-Pad27)") (class "Default")
      (node (ref "U1") (pin "27") (pinfunction "IO16_27") (pintype "passive+no_connect"))
    )
    (net (code "63") (name "unconnected-(U1-IO19-Pad31)") (class "Default")
      (node (ref "U1") (pin "31") (pinfunction "IO19_31") (pintype "passive+no_connect"))
    )
    (net (code "64") (name "unconnected-(U1-IO23-Pad37)") (class "Default")
      (node (ref "U1") (pin "37") (pinfunction "IO23_37") (pintype "passive+no_connect"))
    )
    (net (code "65") (name "unconnected-(U1-NC-Pad32)") (class "Default")
      (node (ref "U1") (pin "32") (pinfunction "NC_32") (pintype "passive+no_connect"))
    )
    (net (code "66") (name "unconnected-(U1-SCK{slash}CLK-Pad20)") (class "Default")
      (node (ref "U1") (pin "20") (pinfunction "SCK/CLK_20") (pintype "passive+no_connect"))
    )
    (net (code "67") (name "unconnected-(U1-SCS{slash}CMD-Pad19)") (class "Default")
      (node (ref "U1") (pin "19") (pinfunction "SCS/CMD_19") (pintype "passive+no_connect"))
    )
    (net (code "68") (name "unconnected-(U1-SDI{slash}SD1-Pad22)") (class "Default")
      (node (ref "U1") (pin "22") (pinfunction "SDI/SD1_22") (pintype "passive+no_connect"))
    )
    (net (code "69") (name "unconnected-(U1-SDO{slash}SD0-Pad21)") (class "Default")
      (node (ref "U1") (pin "21") (pinfunction "SDO/SD0_21") (pintype "passive+no_connect"))
    )
    (net (code "70") (name "unconnected-(U1-SENSOR_VN-Pad5)") (class "Default")
      (node (ref "U1") (pin "5") (pinfunction "SENSOR_VN_5") (pintype "passive+no_connect"))
    )
    (net (code "71") (name "unconnected-(U1-SENSOR_VP-Pad4)") (class "Default")
      (node (ref "U1") (pin "4") (pinfunction "SENSOR_VP_4") (pintype "passive+no_connect"))
    )
    (net (code "72") (name "unconnected-(U1-SHD{slash}SD2-Pad17)") (class "Default")
      (node (ref "U1") (pin "17") (pinfunction "SHD/SD2_17") (pintype "passive+no_connect"))
    )
    (net (code "73") (name "unconnected-(U1-SWP{slash}SD3-Pad18)") (class "Default")
      (node (ref "U1") (pin "18") (pinfunction "SWP/SD3_18") (pintype "passive+no_connect"))
    )
    (net (code "74") (name "unconnected-(U2-ENA-Pad5)") (class "Default")
      (node (ref "U2") (pin "5") (pinfunction "ENA_5") (pintype "passive+no_connect"))
    )
    (net (code "75") (name "unconnected-(U2-NC-Pad2)") (class "Default")
      (node (ref "U2") (pin "2") (pinfunction "NC_2") (pintype "passive+no_connect"))
    )
    (net (code "76") (name "unconnected-(U2-NC-Pad3)") (class "Default")
      (node (ref "U2") (pin "3") (pinfunction "NC_3") (pintype "passive+no_connect"))
    )
    (net (code "77") (name "unconnected-(U9-OUT-Pad3)") (class "Default")
      (node (ref "U9") (pin "3") (pinfunction "OUT_3") (pintype "passive+no_connect"))
    )
    (net (code "78") (name "unconnected-(U9-PGO-Pad5)") (class "Default")
      (node (ref "U9") (pin "5") (pinfunction "PGO_5") (pintype "passive+no_connect"))
    )
    (net (code "79") (name "unconnected-(U10-RST-Pad9)") (class "Default")
      (node (ref "U10") (pin "9") (pinfunction "RST_9") (pintype "passive+no_connect"))
    )
    (net (code "80") (name "unconnected-(U14-Pad3)") (class "Default")
      (node (ref "U14") (pin "3") (pinfunction "3_3") (pintype "passive+no_connect"))
    )
    (net (code "81") (name "unconnected-(U14-Pad4)") (class "Default")
      (node (ref "U14") (pin "4") (pinfunction "4_4") (pintype "passive+no_connect"))
    )
  )
)
